# e-book_schema_v21.net
KiCad netlist of a schematic drawn in EAGLE
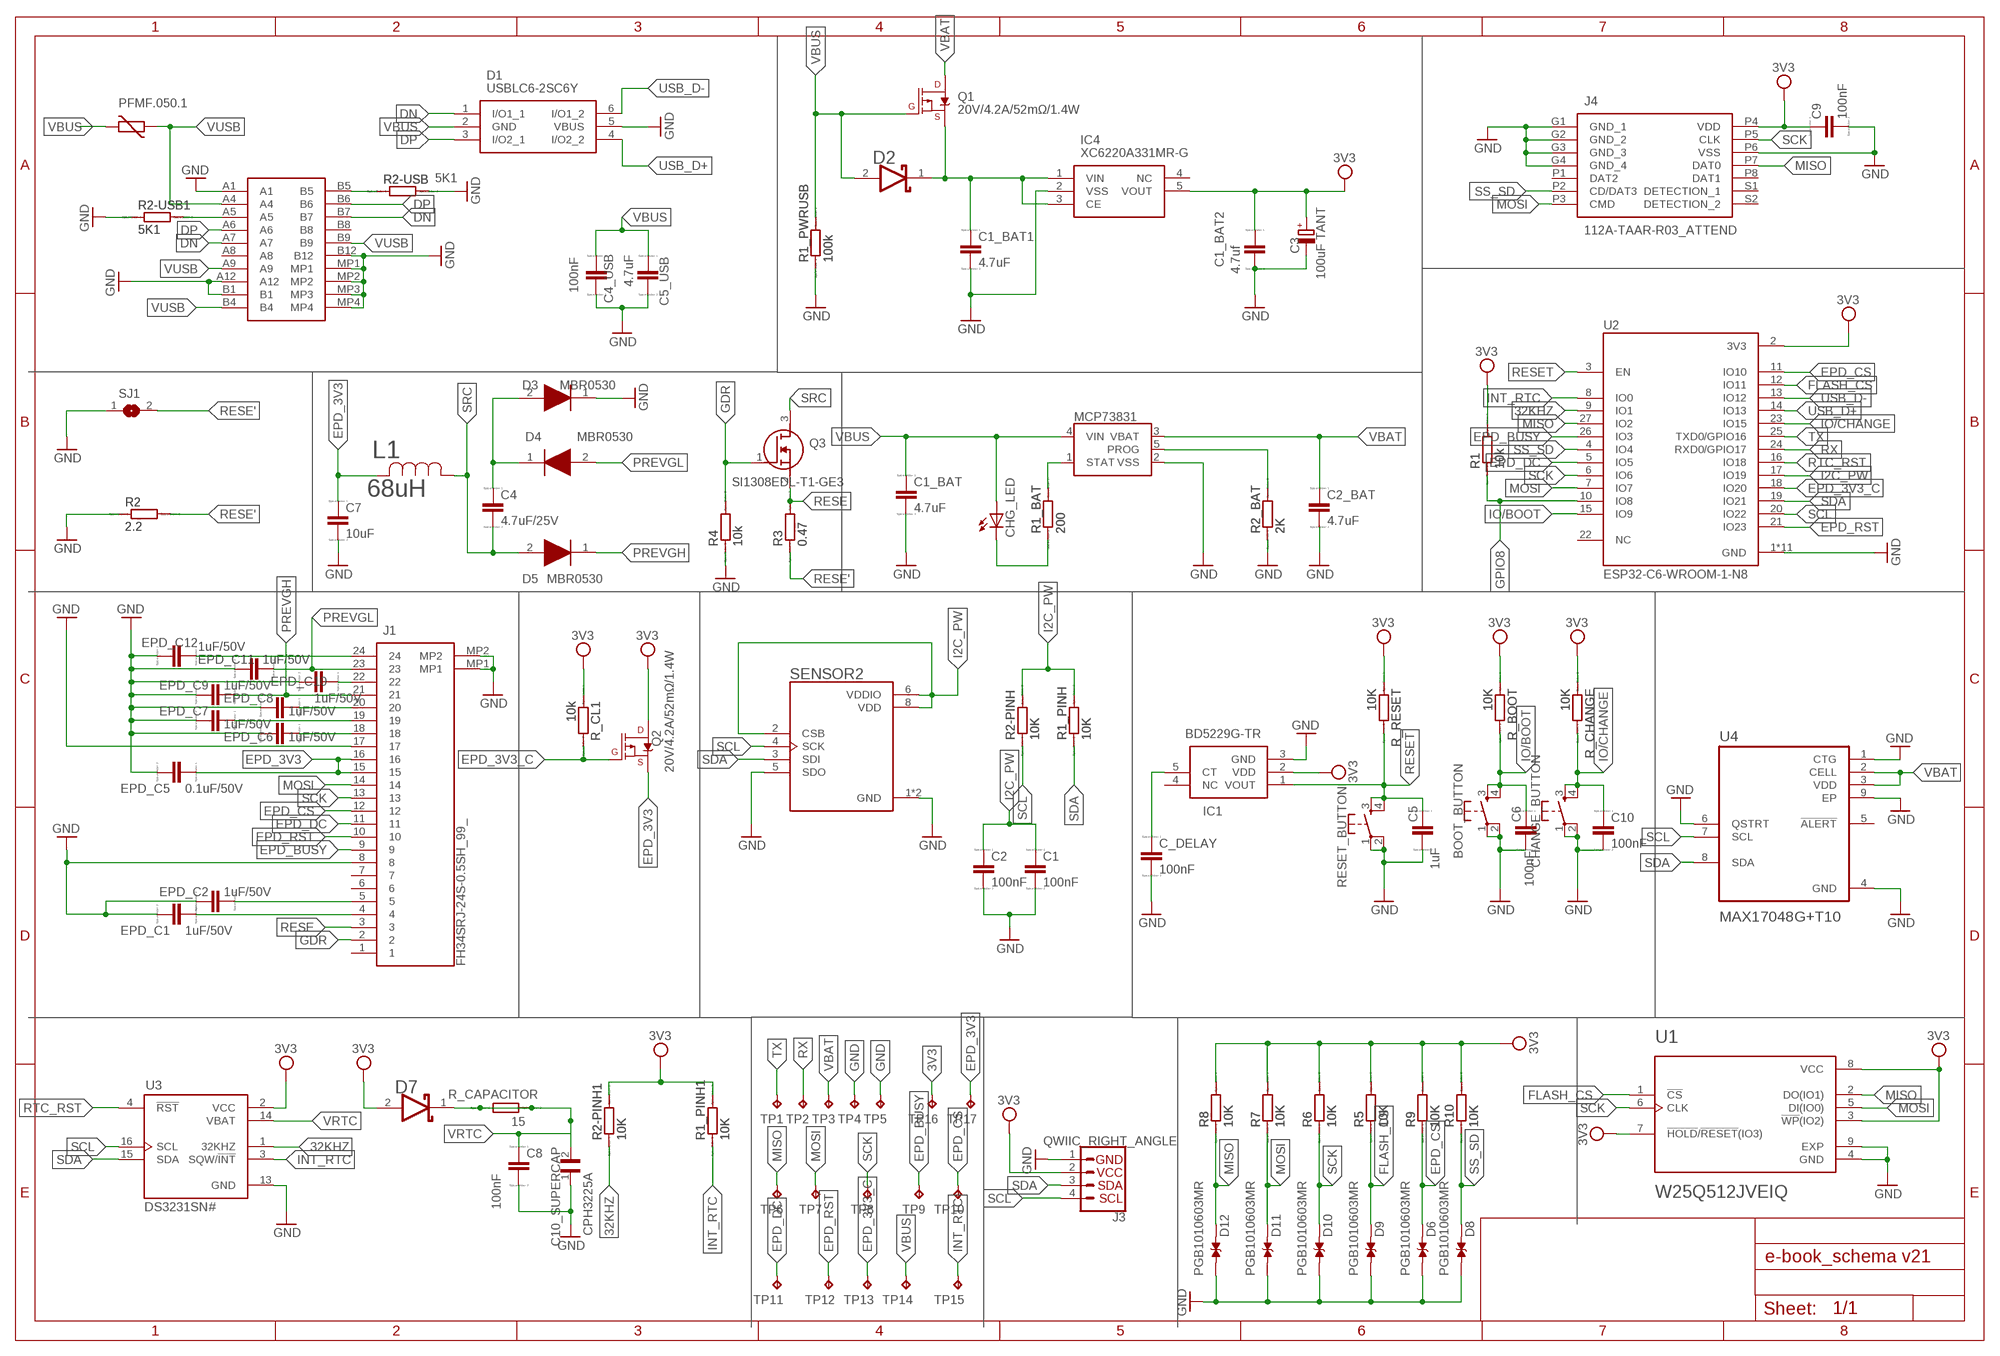
[diagram p0: schematic, sheet 1]

(export (version "E")
  (design (tool "Eeschema 10.0.6"))
  (components
    (comp (ref "BOOT_BUTTON")
      (value "BUTTON_CUSYOMV1")
      (footprint "eagle-import:MYBUTTON")
      (libsource (lib "eagle-import") (part "BUTTON_CUSYOMV1"))
    )
    (comp (ref "C1")
      (value "100nF")
      (footprint "eagle-import:EAGLE-LTSPICE_C0402")
      (libsource (lib "eagle-import") (part "EAGLE-LTSPICE_CC0402"))
    )
    (comp (ref "C1_BAT")
      (value "4.7uF")
      (footprint "eagle-import:EAGLE-LTSPICE_C0402")
      (libsource (lib "eagle-import") (part "EAGLE-LTSPICE_CC0402"))
    )
    (comp (ref "C1_BAT1")
      (value "4.7uF")
      (footprint "eagle-import:EAGLE-LTSPICE_C0402")
      (libsource (lib "eagle-import") (part "EAGLE-LTSPICE_CC0402"))
    )
    (comp (ref "C1_BAT2")
      (value "4.7uf")
      (footprint "eagle-import:EAGLE-LTSPICE_C0402")
      (libsource (lib "eagle-import") (part "EAGLE-LTSPICE_CC0402"))
    )
    (comp (ref "C2")
      (value "100nF")
      (footprint "eagle-import:EAGLE-LTSPICE_C0402")
      (libsource (lib "eagle-import") (part "EAGLE-LTSPICE_CC0402"))
    )
    (comp (ref "C2_BAT")
      (value "4.7uF")
      (footprint "eagle-import:EAGLE-LTSPICE_C0402")
      (libsource (lib "eagle-import") (part "EAGLE-LTSPICE_CC0402"))
    )
    (comp (ref "C3")
      (value "100uF TANT")
      (footprint "eagle-import:RCL_CT3528")
      (libsource (lib "eagle-import") (part "RCL_CPOL-EUCT3528"))
    )
    (comp (ref "C4")
      (value "4.7uF/25V")
      (footprint "eagle-import:EAGLE-LTSPICE_C0402")
      (libsource (lib "eagle-import") (part "EAGLE-LTSPICE_CC0402"))
    )
    (comp (ref "C4_USB")
      (value "100nF")
      (footprint "eagle-import:EAGLE-LTSPICE_C0402")
      (libsource (lib "eagle-import") (part "EAGLE-LTSPICE_CC0402"))
    )
    (comp (ref "C5")
      (value "1uF")
      (footprint "eagle-import:EAGLE-LTSPICE_C0402")
      (libsource (lib "eagle-import") (part "EAGLE-LTSPICE_CC0402"))
    )
    (comp (ref "C5_USB")
      (value "4.7uF")
      (footprint "eagle-import:EAGLE-LTSPICE_C0402")
      (libsource (lib "eagle-import") (part "EAGLE-LTSPICE_CC0402"))
    )
    (comp (ref "C6")
      (value "100nF")
      (footprint "eagle-import:EAGLE-LTSPICE_C0402")
      (libsource (lib "eagle-import") (part "EAGLE-LTSPICE_CC0402"))
    )
    (comp (ref "C7")
      (value "10uF")
      (footprint "eagle-import:EAGLE-LTSPICE_C0402")
      (libsource (lib "eagle-import") (part "EAGLE-LTSPICE_CC0402"))
    )
    (comp (ref "C8")
      (value "100nF")
      (footprint "eagle-import:EAGLE-LTSPICE_C0402")
      (libsource (lib "eagle-import") (part "EAGLE-LTSPICE_CC0402"))
    )
    (comp (ref "C9")
      (value "100nF")
      (footprint "eagle-import:EAGLE-LTSPICE_C0402")
      (libsource (lib "eagle-import") (part "EAGLE-LTSPICE_CC0402"))
    )
    (comp (ref "C10")
      (value "100nF")
      (footprint "eagle-import:EAGLE-LTSPICE_C0402")
      (libsource (lib "eagle-import") (part "EAGLE-LTSPICE_CC0402"))
    )
    (comp (ref "C10_SUPERCAP")
      (value "CPH3225A")
      (footprint "eagle-import:CAPCP3225X100N")
      (fields (field (name "MF") "Seiko Instruments"))
      (libsource (lib "eagle-import") (part "CPH3225A"))
    )
    (comp (ref "CHANGE_BUTTON")
      (value "BUTTON_CUSYOMV1")
      (footprint "eagle-import:MYBUTTON")
      (libsource (lib "eagle-import") (part "BUTTON_CUSYOMV1"))
    )
    (comp (ref "CHG_LED")
      (value "ADAFRUIT_LEDCHIP-LED0603")
      (footprint "eagle-import:ADAFRUIT_CHIP-LED0603")
      (libsource (lib "eagle-import") (part "ADAFRUIT_LEDCHIP-LED0603"))
    )
    (comp (ref "C_DELAY")
      (value "100nF")
      (footprint "eagle-import:EAGLE-LTSPICE_C0402")
      (libsource (lib "eagle-import") (part "EAGLE-LTSPICE_CC0402"))
    )
    (comp (ref "D1")
      (value "USBLC6-2SC6Y")
      (footprint "eagle-import:SOT95P280X145-6N")
      (fields (field (name "MF") "STMicroelectronics"))
      (libsource (lib "eagle-import") (part "USBLC6-2SC6Y"))
    )
    (comp (ref "D2")
      (value "ESP32_WROVER_AVX---SD0805S020S1R0_AVX_SD0805S020S1R0_0_0AVX_SD0805S020S1R0_0_0")
      (footprint "eagle-import:ESP32_WROVER_AVX---SD0805S020S1R0_AVX_SD0805S020S1R0_0")
      (fields
        (field (name "DIGIKEY_PART_NUMBER") "478-7800-1-ND")
        (field (name "MF") "AVX")
        (field (name "MOUSER_PART_NUMBER") "581-SD0805S020S1R0")
      )
      (libsource (lib "eagle-import") (part "ESP32_WROVER_AVX---SD0805S020S1R0_AVX_SD0805S020S1R0_0_0AVX_SD0805S020S1R0_0_0"))
    )
    (comp (ref "D3")
      (value "MBR0530")
      (footprint "eagle-import:SOD3716X135N")
      (fields (field (name "MF") "ON Semiconductor"))
      (libsource (lib "eagle-import") (part "MBR0530"))
    )
    (comp (ref "D4")
      (value "MBR0530")
      (footprint "eagle-import:SOD3716X135N")
      (fields (field (name "MF") "ON Semiconductor"))
      (libsource (lib "eagle-import") (part "MBR0530"))
    )
    (comp (ref "D5")
      (value "MBR0530")
      (footprint "eagle-import:SOD3716X135N")
      (fields (field (name "MF") "ON Semiconductor"))
      (libsource (lib "eagle-import") (part "MBR0530"))
    )
    (comp (ref "D6")
      (value "PGB1010603MR")
      (footprint "eagle-import:DIOC1608X36N")
      (fields (field (name "MF") "Littelfuse Inc."))
      (libsource (lib "eagle-import") (part "PGB1010603MR"))
    )
    (comp (ref "D7")
      (value "ESP32_WROVER_AVX---SD0805S020S1R0_AVX_SD0805S020S1R0_0_0AVX_SD0805S020S1R0_0_0")
      (footprint "eagle-import:ESP32_WROVER_AVX---SD0805S020S1R0_AVX_SD0805S020S1R0_0")
      (fields
        (field (name "DIGIKEY_PART_NUMBER") "478-7800-1-ND")
        (field (name "MF") "AVX")
        (field (name "MOUSER_PART_NUMBER") "581-SD0805S020S1R0")
      )
      (libsource (lib "eagle-import") (part "ESP32_WROVER_AVX---SD0805S020S1R0_AVX_SD0805S020S1R0_0_0AVX_SD0805S020S1R0_0_0"))
    )
    (comp (ref "D8")
      (value "PGB1010603MR")
      (footprint "eagle-import:DIOC1608X36N")
      (fields (field (name "MF") "Littelfuse Inc."))
      (libsource (lib "eagle-import") (part "PGB1010603MR"))
    )
    (comp (ref "D9")
      (value "PGB1010603MR")
      (footprint "eagle-import:DIOC1608X36N")
      (fields (field (name "MF") "Littelfuse Inc."))
      (libsource (lib "eagle-import") (part "PGB1010603MR"))
    )
    (comp (ref "D10")
      (value "PGB1010603MR")
      (footprint "eagle-import:DIOC1608X36N")
      (fields (field (name "MF") "Littelfuse Inc."))
      (libsource (lib "eagle-import") (part "PGB1010603MR"))
    )
    (comp (ref "D11")
      (value "PGB1010603MR")
      (footprint "eagle-import:DIOC1608X36N")
      (fields (field (name "MF") "Littelfuse Inc."))
      (libsource (lib "eagle-import") (part "PGB1010603MR"))
    )
    (comp (ref "D12")
      (value "PGB1010603MR")
      (footprint "eagle-import:DIOC1608X36N")
      (fields (field (name "MF") "Littelfuse Inc."))
      (libsource (lib "eagle-import") (part "PGB1010603MR"))
    )
    (comp (ref "EPD_C1")
      (value "1uF/50V")
      (footprint "eagle-import:EAGLE-LTSPICE_C0402")
      (libsource (lib "eagle-import") (part "EAGLE-LTSPICE_CC0402"))
    )
    (comp (ref "EPD_C2")
      (value "1uF/50V")
      (footprint "eagle-import:EAGLE-LTSPICE_C0402")
      (libsource (lib "eagle-import") (part "EAGLE-LTSPICE_CC0402"))
    )
    (comp (ref "EPD_C5")
      (value "0.1uF/50V")
      (footprint "eagle-import:EAGLE-LTSPICE_C0402")
      (libsource (lib "eagle-import") (part "EAGLE-LTSPICE_CC0402"))
    )
    (comp (ref "EPD_C6")
      (value "1uF/50V")
      (footprint "eagle-import:EAGLE-LTSPICE_C0402")
      (libsource (lib "eagle-import") (part "EAGLE-LTSPICE_CC0402"))
    )
    (comp (ref "EPD_C7")
      (value "1uF/50V")
      (footprint "eagle-import:EAGLE-LTSPICE_C0402")
      (libsource (lib "eagle-import") (part "EAGLE-LTSPICE_CC0402"))
    )
    (comp (ref "EPD_C8")
      (value "1uF/50V")
      (footprint "eagle-import:EAGLE-LTSPICE_C0402")
      (libsource (lib "eagle-import") (part "EAGLE-LTSPICE_CC0402"))
    )
    (comp (ref "EPD_C9")
      (value "1uF/50V")
      (footprint "eagle-import:EAGLE-LTSPICE_C0402")
      (libsource (lib "eagle-import") (part "EAGLE-LTSPICE_CC0402"))
    )
    (comp (ref "EPD_C10")
      (value "1uF/50V")
      (footprint "eagle-import:EAGLE-LTSPICE_C0402")
      (libsource (lib "eagle-import") (part "EAGLE-LTSPICE_CC0402"))
    )
    (comp (ref "EPD_C11")
      (value "1uF/50V")
      (footprint "eagle-import:EAGLE-LTSPICE_C0402")
      (libsource (lib "eagle-import") (part "EAGLE-LTSPICE_CC0402"))
    )
    (comp (ref "EPD_C12")
      (value "1uF/50V")
      (footprint "eagle-import:EAGLE-LTSPICE_C0402")
      (libsource (lib "eagle-import") (part "EAGLE-LTSPICE_CC0402"))
    )
    (comp (ref "IC1")
      (value "BD5229G-TR")
      (footprint "eagle-import:SOT95P280X125-5N")
      (fields (field (name "MOUSER_PART_NUMBER") "755-BD5229G-TR"))
      (libsource (lib "eagle-import") (part "BD5229G-TR"))
    )
    (comp (ref "IC4")
      (value "XC6220A331MR-G")
      (footprint "eagle-import:SOT95P280X120-5N")
      (fields (field (name "MOUSER_PART_NUMBER") "865-XC6220A331MR-G"))
      (libsource (lib "eagle-import") (part "XC6220A331MR-G"))
    )
    (comp (ref "J1")
      (value "FH34SRJ-24S-0.5SH_99_")
      (footprint "eagle-import:FH34SRJ24S05SH99")
      (fields
        (field (name "MANUFACTURER_PART_NUMBER") "FH34SRJ-24S-0.5SH(99)")
        (field (name "MOUSER_PART_NUMBER") "798-FH34SRJ24S05SH99")
      )
      (libsource (lib "eagle-import") (part "FH34SRJ-24S-0.5SH_99_"))
    )
    (comp (ref "J2")
      (value "SAMACSYS_PARTS_USB4110-GF-A")
      (footprint "eagle-import:SAMACSYS_PARTS_USB4110GFA")
      (fields
        (field (name "MANUFACTURER_PART_NUMBER") "USB4110-GF-A")
        (field (name "MOUSER_PART_NUMBER") "640-USB4110-GF-A")
      )
      (libsource (lib "eagle-import") (part "SAMACSYS_PARTS_USB4110-GF-A"))
    )
    (comp (ref "J3")
      (value "QWIIC_RIGHT_ANGLE")
      (footprint "eagle-import:JST04_1MM_RA")
      (libsource (lib "eagle-import") (part "QWIIC_CONNECTORJS-1MM"))
    )
    (comp (ref "J4")
      (value "112A-TAAR-R03_ATTEND")
      (footprint "eagle-import:112ATAARR03ATTEND")
      (fields (field (name "MANUFACTURER_PART_NUMBER") "112A-TAAR-R03 ATTEND"))
      (libsource (lib "eagle-import") (part "112A-TAAR-R03_ATTEND"))
    )
    (comp (ref "L1")
      (value "68uH")
      (footprint "eagle-import:IND_4828-WE-TPC_WRE")
      (fields
        (field (name "MANUFACTURER_PART_NUMBER") "744043680")
        (field (name "COPYRIGHT") "Copyright (C) 2024 Ultra Librarian. All rights reserved.")
      )
      (libsource (lib "eagle-import") (part "744043680IND_4828-WE-TPC_WRE"))
    )
    (comp (ref "MCP73831")
      (value "ESP32_WROVER_SPARKFUN-IC-POWER_MCP73831")
      (footprint "eagle-import:ESP32_WROVER_SPARKFUN-IC-POWER_SOT23-5")
      (libsource (lib "eagle-import") (part "ESP32_WROVER_SPARKFUN-IC-POWER_MCP73831"))
    )
    (comp (ref "PFMF.050.1")
      (value "ESP32C6_VARISTORCN1812")
      (footprint "eagle-import:ESP32C6_VARISTOR_CT_CN1812")
      (libsource (lib "eagle-import") (part "ESP32C6_VARISTORCN1812"))
    )
    (comp (ref "Q1")
      (value "20V/4.2A/52mΩ/1.4W")
      (footprint "eagle-import:ESP32_WROVER_SPARKFUN-DISCRETESEMI_SOT23-3")
      (libsource (lib "eagle-import") (part "ESP32_WROVER_SPARKFUN-DISCRETESEMI_MOSFET_PCH-DMG2305UX-7"))
    )
    (comp (ref "Q2")
      (value "20V/4.2A/52mΩ/1.4W")
      (footprint "eagle-import:ESP32_WROVER_SPARKFUN-DISCRETESEMI_SOT23-3")
      (libsource (lib "eagle-import") (part "ESP32_WROVER_SPARKFUN-DISCRETESEMI_MOSFET_PCH-DMG2305UX-7"))
    )
    (comp (ref "Q3")
      (value "SI1308EDL-T1-GE3")
      (footprint "eagle-import:SOT65P210X110-3N")
      (fields (field (name "MF") "Vishay Siliconix"))
      (libsource (lib "eagle-import") (part "SI1308EDL-T1-GE3"))
    )
    (comp (ref "R1")
      (value "10k")
      (footprint "eagle-import:ESP32_WROVER_EAGLE-LTSPICE_R0402")
      (libsource (lib "eagle-import") (part "ESP32_WROVER_EAGLE-LTSPICE_RR0402"))
    )
    (comp (ref "R1_BAT")
      (value "200")
      (footprint "eagle-import:ESP32_WROVER_EAGLE-LTSPICE_R0402")
      (libsource (lib "eagle-import") (part "ESP32_WROVER_EAGLE-LTSPICE_RR0402"))
    )
    (comp (ref "R1_PINH")
      (value "10K")
      (footprint "eagle-import:ESP32_WROVER_EAGLE-LTSPICE_R0402")
      (libsource (lib "eagle-import") (part "ESP32_WROVER_EAGLE-LTSPICE_RR0402"))
    )
    (comp (ref "R1_PINH1")
      (value "10K")
      (footprint "eagle-import:ESP32_WROVER_EAGLE-LTSPICE_R0402")
      (libsource (lib "eagle-import") (part "ESP32_WROVER_EAGLE-LTSPICE_RR0402"))
    )
    (comp (ref "R1_PWRUSB")
      (value "100k")
      (footprint "eagle-import:ESP32_WROVER_EAGLE-LTSPICE_R0402")
      (libsource (lib "eagle-import") (part "ESP32_WROVER_EAGLE-LTSPICE_RR0402"))
    )
    (comp (ref "R2")
      (value "2.2")
      (footprint "eagle-import:ESP32_WROVER_EAGLE-LTSPICE_R0402")
      (libsource (lib "eagle-import") (part "ESP32_WROVER_EAGLE-LTSPICE_RR0402"))
    )
    (comp (ref "R2-PINH")
      (value "10K")
      (footprint "eagle-import:ESP32_WROVER_EAGLE-LTSPICE_R0402")
      (libsource (lib "eagle-import") (part "ESP32_WROVER_EAGLE-LTSPICE_RR0402"))
    )
    (comp (ref "R2-PINH1")
      (value "10K")
      (footprint "eagle-import:ESP32_WROVER_EAGLE-LTSPICE_R0402")
      (libsource (lib "eagle-import") (part "ESP32_WROVER_EAGLE-LTSPICE_RR0402"))
    )
    (comp (ref "R2-USB")
      (value "5K1")
      (footprint "eagle-import:ESP32_WROVER_EAGLE-LTSPICE_R0402")
      (libsource (lib "eagle-import") (part "ESP32_WROVER_EAGLE-LTSPICE_RR0402"))
    )
    (comp (ref "R2-USB1")
      (value "5K1")
      (footprint "eagle-import:ESP32_WROVER_EAGLE-LTSPICE_R0402")
      (libsource (lib "eagle-import") (part "ESP32_WROVER_EAGLE-LTSPICE_RR0402"))
    )
    (comp (ref "R2_BAT")
      (value "2K")
      (footprint "eagle-import:ESP32_WROVER_EAGLE-LTSPICE_R0402")
      (libsource (lib "eagle-import") (part "ESP32_WROVER_EAGLE-LTSPICE_RR0402"))
    )
    (comp (ref "R3")
      (value "0.47")
      (footprint "eagle-import:ESP32_WROVER_EAGLE-LTSPICE_R0402")
      (libsource (lib "eagle-import") (part "ESP32_WROVER_EAGLE-LTSPICE_RR0402"))
    )
    (comp (ref "R4")
      (value "10k")
      (footprint "eagle-import:ESP32_WROVER_EAGLE-LTSPICE_R0402")
      (libsource (lib "eagle-import") (part "ESP32_WROVER_EAGLE-LTSPICE_RR0402"))
    )
    (comp (ref "R5")
      (value "10K")
      (footprint "eagle-import:ESP32_WROVER_EAGLE-LTSPICE_R0402")
      (libsource (lib "eagle-import") (part "ESP32_WROVER_EAGLE-LTSPICE_RR0402"))
    )
    (comp (ref "R6")
      (value "10K")
      (footprint "eagle-import:ESP32_WROVER_EAGLE-LTSPICE_R0402")
      (libsource (lib "eagle-import") (part "ESP32_WROVER_EAGLE-LTSPICE_RR0402"))
    )
    (comp (ref "R7")
      (value "10K")
      (footprint "eagle-import:ESP32_WROVER_EAGLE-LTSPICE_R0402")
      (libsource (lib "eagle-import") (part "ESP32_WROVER_EAGLE-LTSPICE_RR0402"))
    )
    (comp (ref "R8")
      (value "10K")
      (footprint "eagle-import:ESP32_WROVER_EAGLE-LTSPICE_R0402")
      (libsource (lib "eagle-import") (part "ESP32_WROVER_EAGLE-LTSPICE_RR0402"))
    )
    (comp (ref "R9")
      (value "10K")
      (footprint "eagle-import:ESP32_WROVER_EAGLE-LTSPICE_R0402")
      (libsource (lib "eagle-import") (part "ESP32_WROVER_EAGLE-LTSPICE_RR0402"))
    )
    (comp (ref "R10")
      (value "10K")
      (footprint "eagle-import:ESP32_WROVER_EAGLE-LTSPICE_R0402")
      (libsource (lib "eagle-import") (part "ESP32_WROVER_EAGLE-LTSPICE_RR0402"))
    )
    (comp (ref "RESET_BUTTON")
      (value "BUTTON_CUSYOMV1")
      (footprint "eagle-import:MYBUTTON")
      (libsource (lib "eagle-import") (part "BUTTON_CUSYOMV1"))
    )
    (comp (ref "R_BOOT")
      (value "10K")
      (footprint "eagle-import:ESP32_WROVER_EAGLE-LTSPICE_R0402")
      (libsource (lib "eagle-import") (part "ESP32_WROVER_EAGLE-LTSPICE_RR0402"))
    )
    (comp (ref "R_CAPACITOR")
      (value "15")
      (footprint "eagle-import:ESP32_WROVER_EAGLE-LTSPICE_R0402")
      (libsource (lib "eagle-import") (part "ESP32_WROVER_EAGLE-LTSPICE_RR0402"))
    )
    (comp (ref "R_CHANGE")
      (value "10K")
      (footprint "eagle-import:ESP32_WROVER_EAGLE-LTSPICE_R0402")
      (libsource (lib "eagle-import") (part "ESP32_WROVER_EAGLE-LTSPICE_RR0402"))
    )
    (comp (ref "R_CL1")
      (value "10k")
      (footprint "eagle-import:ESP32_WROVER_EAGLE-LTSPICE_R0402")
      (libsource (lib "eagle-import") (part "ESP32_WROVER_EAGLE-LTSPICE_RR0402"))
    )
    (comp (ref "R_RESET")
      (value "10K")
      (footprint "eagle-import:ESP32_WROVER_EAGLE-LTSPICE_R0402")
      (libsource (lib "eagle-import") (part "ESP32_WROVER_EAGLE-LTSPICE_RR0402"))
    )
    (comp (ref "SENSOR2")
      (value "ESP32_WROVER_BME680_BME680")
      (footprint "eagle-import:ESP32_WROVER_BME680_PSON80P300X300X100-8N")
      (fields (field (name "MF") "Bosch Sensortec") (field (name "MP") "BME680"))
      (libsource (lib "eagle-import") (part "ESP32_WROVER_BME680_BME680"))
    )
    (comp (ref "SJ1") (value "SJ") (footprint "eagle-import:SJ") (libsource (lib "eagle-import") (part "SJ")))
    (comp (ref "TP1")
      (value "TPTP20R")
      (footprint "eagle-import:TP20R")
      (libsource (lib "eagle-import") (part "TPTP20R"))
    )
    (comp (ref "TP2")
      (value "TPTP20R")
      (footprint "eagle-import:TP20R")
      (libsource (lib "eagle-import") (part "TPTP20R"))
    )
    (comp (ref "TP3")
      (value "TPTP20R")
      (footprint "eagle-import:TP20R")
      (libsource (lib "eagle-import") (part "TPTP20R"))
    )
    (comp (ref "TP4")
      (value "TPTP20R")
      (footprint "eagle-import:TP20R")
      (libsource (lib "eagle-import") (part "TPTP20R"))
    )
    (comp (ref "TP5")
      (value "TPTP20R")
      (footprint "eagle-import:TP20R")
      (libsource (lib "eagle-import") (part "TPTP20R"))
    )
    (comp (ref "TP6")
      (value "TPTP20R")
      (footprint "eagle-import:TP20R")
      (libsource (lib "eagle-import") (part "TPTP20R"))
    )
    (comp (ref "TP7")
      (value "TPTP20R")
      (footprint "eagle-import:TP20R")
      (libsource (lib "eagle-import") (part "TPTP20R"))
    )
    (comp (ref "TP8")
      (value "TPTP20R")
      (footprint "eagle-import:TP20R")
      (libsource (lib "eagle-import") (part "TPTP20R"))
    )
    (comp (ref "TP9")
      (value "TPTP20R")
      (footprint "eagle-import:TP20R")
      (libsource (lib "eagle-import") (part "TPTP20R"))
    )
    (comp (ref "TP10")
      (value "TPTP20R")
      (footprint "eagle-import:TP20R")
      (libsource (lib "eagle-import") (part "TPTP20R"))
    )
    (comp (ref "TP11")
      (value "TPTP20R")
      (footprint "eagle-import:TP20R")
      (libsource (lib "eagle-import") (part "TPTP20R"))
    )
    (comp (ref "TP12")
      (value "TPTP20R")
      (footprint "eagle-import:TP20R")
      (libsource (lib "eagle-import") (part "TPTP20R"))
    )
    (comp (ref "TP13")
      (value "TPTP20R")
      (footprint "eagle-import:TP20R")
      (libsource (lib "eagle-import") (part "TPTP20R"))
    )
    (comp (ref "TP14")
      (value "TPTP20R")
      (footprint "eagle-import:TP20R")
      (libsource (lib "eagle-import") (part "TPTP20R"))
    )
    (comp (ref "TP15")
      (value "TPTP20R")
      (footprint "eagle-import:TP20R")
      (libsource (lib "eagle-import") (part "TPTP20R"))
    )
    (comp (ref "TP16")
      (value "TPTP20R")
      (footprint "eagle-import:TP20R")
      (libsource (lib "eagle-import") (part "TPTP20R"))
    )
    (comp (ref "TP17")
      (value "TPTP20R")
      (footprint "eagle-import:TP20R")
      (libsource (lib "eagle-import") (part "TPTP20R"))
    )
    (comp (ref "U1")
      (value "W25Q512JVEIQ")
      (footprint "eagle-import:SON127P600X800X80-9N")
      (fields (field (name "MF") "Winbond Electronics"))
      (libsource (lib "eagle-import") (part "W25Q512JVEIQ"))
    )
    (comp (ref "U2")
      (value "ESP32-C6-WROOM-1-N8")
      (footprint "eagle-import:XCVR_ESP32-C6-WROOM-1-N8")
      (fields (field (name "MF") "Espressif Systems"))
      (libsource (lib "eagle-import") (part "ESP32-C6-WROOM-1-N8"))
    )
    (comp (ref "U3")
      (value "DS3231SN#")
      (footprint "eagle-import:SOIC127P1032X265-16N")
      (fields (field (name "MF") "Analog Devices"))
      (libsource (lib "eagle-import") (part "DS3231SN#"))
    )
    (comp (ref "U4")
      (value "MAX17048G+T10")
      (footprint "eagle-import:SON50P200X200X80-9N")
      (fields (field (name "MF") "Analog Devices"))
      (libsource (lib "eagle-import") (part "MAX17048G+T10"))
    )
  )
  (nets
    (net (code "1") (name "3V3") (class "Default")
      (node (ref "C1_BAT2") (pin "1") (pinfunction "1_1") (pintype "passive"))
      (node (ref "C3") (pin "+") (pinfunction "+_+") (pintype "passive"))
      (node (ref "C9") (pin "1") (pinfunction "1_1") (pintype "passive"))
      (node (ref "D7") (pin "2") (pinfunction "ANODE_2") (pintype "bidirectional"))
      (node (ref "IC1") (pin "2") (pinfunction "VDD_2") (pintype "bidirectional"))
      (node (ref "IC4") (pin "5") (pinfunction "VOUT_5") (pintype "bidirectional"))
      (node (ref "J3") (pin "2") (pinfunction "2_2") (pintype "power_in"))
      (node (ref "J4") (pin "P4") (pinfunction "VDD_P4") (pintype "bidirectional"))
      (node (ref "Q2") (pin "3") (pinfunction "D_3") (pintype "bidirectional"))
      (node (ref "R1") (pin "2") (pinfunction "2_2") (pintype "passive"))
      (node (ref "R10") (pin "2") (pinfunction "2_2") (pintype "passive"))
      (node (ref "R1_PINH1") (pin "2") (pinfunction "2_2") (pintype "passive"))
      (node (ref "R2-PINH1") (pin "2") (pinfunction "2_2") (pintype "passive"))
      (node (ref "R5") (pin "2") (pinfunction "2_2") (pintype "passive"))
      (node (ref "R6") (pin "2") (pinfunction "2_2") (pintype "passive"))
      (node (ref "R7") (pin "2") (pinfunction "2_2") (pintype "passive"))
      (node (ref "R8") (pin "2") (pinfunction "2_2") (pintype "passive"))
      (node (ref "R9") (pin "2") (pinfunction "2_2") (pintype "passive"))
      (node (ref "R_BOOT") (pin "1") (pinfunction "1_1") (pintype "passive"))
      (node (ref "R_CHANGE") (pin "1") (pinfunction "1_1") (pintype "passive"))
      (node (ref "R_CL1") (pin "1") (pinfunction "1_1") (pintype "passive"))
      (node (ref "R_RESET") (pin "1") (pinfunction "1_1") (pintype "passive"))
      (node (ref "TP16") (pin "TP") (pinfunction "TP_TP") (pintype "input"))
      (node (ref "U1") (pin "3") (pinfunction "~{WP}(IO2)_3") (pintype "bidirectional"))
      (node (ref "U1") (pin "7") (pinfunction "~{HOLD}/~{RESET}(IO3)_7") (pintype "bidirectional"))
      (node (ref "U1") (pin "8") (pinfunction "VCC_8") (pintype "power_in"))
      (node (ref "U2") (pin "2") (pinfunction "3V3_2") (pintype "power_in"))
      (node (ref "U3") (pin "2") (pinfunction "VCC_2") (pintype "power_in"))
    )
    (net (code "2") (name "32KHZ") (class "Default")
      (node (ref "R2-PINH1") (pin "1") (pinfunction "1_1") (pintype "passive"))
      (node (ref "U2") (pin "9") (pinfunction "IO1_9") (pintype "bidirectional"))
      (node (ref "U3") (pin "1") (pinfunction "32KHZ_1") (pintype "output"))
    )
    (net (code "3") (name "DN") (class "Default")
      (node (ref "D1") (pin "1") (pinfunction "I/O1_1_1") (pintype "bidirectional"))
      (node (ref "J2") (pin "A7") (pinfunction "A7_A7") (pintype "bidirectional"))
      (node (ref "J2") (pin "B7") (pinfunction "B7_B7") (pintype "bidirectional"))
    )
    (net (code "4") (name "DP") (class "Default")
      (node (ref "D1") (pin "3") (pinfunction "I/O2_1_3") (pintype "bidirectional"))
      (node (ref "J2") (pin "A6") (pinfunction "A6_A6") (pintype "bidirectional"))
      (node (ref "J2") (pin "B6") (pinfunction "B6_B6") (pintype "bidirectional"))
    )
    (net (code "5") (name "EPD_3V3") (class "Default")
      (node (ref "C7") (pin "1") (pinfunction "1_1") (pintype "passive"))
      (node (ref "EPD_C5") (pin "1") (pinfunction "1_1") (pintype "passive"))
      (node (ref "J1") (pin "15") (pinfunction "15_15") (pintype "bidirectional"))
      (node (ref "J1") (pin "16") (pinfunction "16_16") (pintype "bidirectional"))
      (node (ref "L1") (pin "2") (pinfunction "2_2") (pintype "passive"))
      (node (ref "Q2") (pin "2") (pinfunction "S_2") (pintype "bidirectional"))
      (node (ref "TP17") (pin "TP") (pinfunction "TP_TP") (pintype "input"))
    )
    (net (code "6") (name "EPD_3V3_C") (class "Default")
      (node (ref "Q2") (pin "1") (pinfunction "G_1") (pintype "bidirectional"))
      (node (ref "R_CL1") (pin "2") (pinfunction "2_2") (pintype "passive"))
      (node (ref "TP13") (pin "TP") (pinfunction "TP_TP") (pintype "input"))
      (node (ref "U2") (pin "18") (pinfunction "IO20_18") (pintype "bidirectional"))
    )
    (net (code "7") (name "EPD_BUSY") (class "Default")
      (node (ref "J1") (pin "9") (pinfunction "9_9") (pintype "bidirectional"))
      (node (ref "TP9") (pin "TP") (pinfunction "TP_TP") (pintype "input"))
      (node (ref "U2") (pin "26") (pinfunction "IO3_26") (pintype "bidirectional"))
    )
    (net (code "8") (name "EPD_CS") (class "Default")
      (node (ref "D6") (pin "2") (pinfunction "2_2") (pintype "passive"))
      (node (ref "J1") (pin "12") (pinfunction "12_12") (pintype "bidirectional"))
      (node (ref "R9") (pin "1") (pinfunction "1_1") (pintype "passive"))
      (node (ref "TP10") (pin "TP") (pinfunction "TP_TP") (pintype "input"))
      (node (ref "U2") (pin "11") (pinfunction "IO10_11") (pintype "bidirectional"))
    )
    (net (code "9") (name "EPD_DC") (class "Default")
      (node (ref "J1") (pin "11") (pinfunction "11_11") (pintype "bidirectional"))
      (node (ref "TP11") (pin "TP") (pinfunction "TP_TP") (pintype "input"))
      (node (ref "U2") (pin "5") (pinfunction "IO5_5") (pintype "bidirectional"))
    )
    (net (code "10") (name "EPD_RST") (class "Default")
      (node (ref "J1") (pin "10") (pinfunction "10_10") (pintype "bidirectional"))
      (node (ref "TP12") (pin "TP") (pinfunction "TP_TP") (pintype "input"))
      (node (ref "U2") (pin "21") (pinfunction "IO23_21") (pintype "bidirectional"))
    )
    (net (code "11") (name "FLASH_CS") (class "Default")
      (node (ref "D9") (pin "2") (pinfunction "2_2") (pintype "passive"))
      (node (ref "R5") (pin "1") (pinfunction "1_1") (pintype "passive"))
      (node (ref "U1") (pin "1") (pinfunction "~{CS}_1") (pintype "input"))
      (node (ref "U2") (pin "12") (pinfunction "IO11_12") (pintype "bidirectional"))
    )
    (net (code "12") (name "GDR") (class "Default")
      (node (ref "J1") (pin "2") (pinfunction "2_2") (pintype "bidirectional"))
      (node (ref "Q3") (pin "1") (pinfunction "G_1") (pintype "bidirectional"))
      (node (ref "R4") (pin "2") (pinfunction "2_2") (pintype "passive"))
    )
    (net (code "13") (name "GND") (class "Default")
      (node (ref "BOOT_BUTTON") (pin "1") (pinfunction "1_1") (pintype "passive"))
      (node (ref "BOOT_BUTTON") (pin "2") (pinfunction "2_2") (pintype "passive"))
      (node (ref "C1") (pin "2") (pinfunction "2_2") (pintype "passive"))
      (node (ref "C10") (pin "2") (pinfunction "2_2") (pintype "passive"))
      (node (ref "C10_SUPERCAP") (pin "1") (pinfunction "1_1") (pintype "passive"))
      (node (ref "C1_BAT") (pin "2") (pinfunction "2_2") (pintype "passive"))
      (node (ref "C1_BAT1") (pin "2") (pinfunction "2_2") (pintype "passive"))
      (node (ref "C1_BAT2") (pin "2") (pinfunction "2_2") (pintype "passive"))
      (node (ref "C2") (pin "2") (pinfunction "2_2") (pintype "passive"))
      (node (ref "C2_BAT") (pin "2") (pinfunction "2_2") (pintype "passive"))
      (node (ref "C3") (pin "-") (pinfunction "-_-") (pintype "passive"))
      (node (ref "C4_USB") (pin "2") (pinfunction "2_2") (pintype "passive"))
      (node (ref "C5") (pin "2") (pinfunction "2_2") (pintype "passive"))
      (node (ref "C5_USB") (pin "2") (pinfunction "2_2") (pintype "passive"))
      (node (ref "C6") (pin "2") (pinfunction "2_2") (pintype "passive"))
      (node (ref "C7") (pin "2") (pinfunction "2_2") (pintype "passive"))
      (node (ref "C8") (pin "2") (pinfunction "2_2") (pintype "passive"))
      (node (ref "C9") (pin "2") (pinfunction "2_2") (pintype "passive"))
      (node (ref "CHANGE_BUTTON") (pin "1") (pinfunction "1_1") (pintype "passive"))
      (node (ref "CHANGE_BUTTON") (pin "2") (pinfunction "2_2") (pintype "passive"))
      (node (ref "C_DELAY") (pin "2") (pinfunction "2_2") (pintype "passive"))
      (node (ref "D1") (pin "5") (pinfunction "VBUS_5") (pintype "bidirectional"))
      (node (ref "D10") (pin "1") (pinfunction "1_1") (pintype "passive"))
      (node (ref "D11") (pin "1") (pinfunction "1_1") (pintype "passive"))
      (node (ref "D12") (pin "1") (pinfunction "1_1") (pintype "passive"))
      (node (ref "D3") (pin "1") (pinfunction "K_1") (pintype "bidirectional"))
      (node (ref "D6") (pin "1") (pinfunction "1_1") (pintype "passive"))
      (node (ref "D8") (pin "1") (pinfunction "1_1") (pintype "passive"))
      (node (ref "D9") (pin "1") (pinfunction "1_1") (pintype "passive"))
      (node (ref "EPD_C1") (pin "2") (pinfunction "2_2") (pintype "passive"))
      (node (ref "EPD_C10") (pin "2") (pinfunction "2_2") (pintype "passive"))
      (node (ref "EPD_C11") (pin "2") (pinfunction "2_2") (pintype "passive"))
      (node (ref "EPD_C12") (pin "2") (pinfunction "2_2") (pintype "passive"))
      (node (ref "EPD_C2") (pin "2") (pinfunction "2_2") (pintype "passive"))
      (node (ref "EPD_C5") (pin "2") (pinfunction "2_2") (pintype "passive"))
      (node (ref "EPD_C6") (pin "2") (pinfunction "2_2") (pintype "passive"))
      (node (ref "EPD_C7") (pin "2") (pinfunction "2_2") (pintype "passive"))
      (node (ref "EPD_C8") (pin "2") (pinfunction "2_2") (pintype "passive"))
      (node (ref "EPD_C9") (pin "2") (pinfunction "2_2") (pintype "passive"))
      (node (ref "IC1") (pin "3") (pinfunction "GND_3") (pintype "bidirectional"))
      (node (ref "IC4") (pin "2") (pinfunction "VSS_2") (pintype "bidirectional"))
      (node (ref "J1") (pin "17") (pinfunction "17_17") (pintype "bidirectional"))
      (node (ref "J1") (pin "8") (pinfunction "8_8") (pintype "bidirectional"))
      (node (ref "J1") (pin "MP1") (pinfunction "MP1_MP1") (pintype "bidirectional"))
      (node (ref "J1") (pin "MP2") (pinfunction "MP2_MP2") (pintype "bidirectional"))
      (node (ref "J2") (pin "A1") (pinfunction "A1_A1") (pintype "bidirectional"))
      (node (ref "J2") (pin "A12") (pinfunction "A12_A12") (pintype "bidirectional"))
      (node (ref "J2") (pin "B1") (pinfunction "B1_B1") (pintype "bidirectional"))
      (node (ref "J2") (pin "B12") (pinfunction "B12_B12") (pintype "bidirectional"))
      (node (ref "J2") (pin "MP1") (pinfunction "MP1_MP1") (pintype "bidirectional"))
      (node (ref "J2") (pin "MP2") (pinfunction "MP2_MP2") (pintype "bidirectional"))
      (node (ref "J2") (pin "MP3") (pinfunction "MP3_MP3") (pintype "bidirectional"))
      (node (ref "J2") (pin "MP4") (pinfunction "MP4_MP4") (pintype "bidirectional"))
      (node (ref "J3") (pin "1") (pinfunction "1_1") (pintype "power_in"))
      (node (ref "J4") (pin "G1") (pinfunction "GND_1_G1") (pintype "bidirectional"))
      (node (ref "J4") (pin "G2") (pinfunction "GND_2_G2") (pintype "bidirectional"))
      (node (ref "J4") (pin "G3") (pinfunction "GND_3_G3") (pintype "bidirectional"))
      (node (ref "J4") (pin "G4") (pinfunction "GND_4_G4") (pintype "bidirectional"))
      (node (ref "J4") (pin "P6") (pinfunction "VSS_P6") (pintype "bidirectional"))
      (node (ref "MCP73831") (pin "2") (pinfunction "VSS_2") (pintype "power_in"))
      (node (ref "R1_PWRUSB") (pin "1") (pinfunction "1_1") (pintype "passive"))
      (node (ref "R2") (pin "1") (pinfunction "1_1") (pintype "passive"))
      (node (ref "R2-USB") (pin "2") (pinfunction "2_2") (pintype "passive"))
      (node (ref "R2-USB1") (pin "1") (pinfunction "1_1") (pintype "passive"))
      (node (ref "R2_BAT") (pin "1") (pinfunction "1_1") (pintype "passive"))
      (node (ref "R4") (pin "1") (pinfunction "1_1") (pintype "passive"))
      (node (ref "RESET_BUTTON") (pin "1") (pinfunction "1_1") (pintype "passive"))
      (node (ref "RESET_BUTTON") (pin "2") (pinfunction "2_2") (pintype "passive"))
      (node (ref "SENSOR2") (pin "1") (pinfunction "GND_1") (pintype "power_in"))
      (node (ref "SENSOR2") (pin "5") (pinfunction "SDO_5") (pintype "bidirectional"))
      (node (ref "SENSOR2") (pin "7") (pinfunction "GND_7") (pintype "power_in"))
      (node (ref "SJ1") (pin "1") (pinfunction "1_1") (pintype "passive"))
      (node (ref "TP4") (pin "TP") (pinfunction "TP_TP") (pintype "input"))
      (node (ref "TP5") (pin "TP") (pinfunction "TP_TP") (pintype "input"))
      (node (ref "U1") (pin "4") (pinfunction "GND_4") (pintype "power_in"))
      (node (ref "U1") (pin "9") (pinfunction "EXP_9") (pintype "passive"))
      (node (ref "U2") (pin "1") (pinfunction "GND_1") (pintype "power_in"))
      (node (ref "U2") (pin "28") (pinfunction "GND_28") (pintype "power_in"))
      (node (ref "U2") (pin "29_1") (pinfunction "GND_29_1") (pintype "power_in"))
      (node (ref "U2") (pin "29_2") (pinfunction "GND_29_2") (pintype "power_in"))
      (node (ref "U2") (pin "29_3") (pinfunction "GND_29_3") (pintype "power_in"))
      (node (ref "U2") (pin "29_4") (pinfunction "GND_29_4") (pintype "power_in"))
      (node (ref "U2") (pin "29_5") (pinfunction "GND_29_5") (pintype "power_in"))
      (node (ref "U2") (pin "29_6") (pinfunction "GND_29_6") (pintype "power_in"))
      (node (ref "U2") (pin "29_7") (pinfunction "GND_29_7") (pintype "power_in"))
      (node (ref "U2") (pin "29_8") (pinfunction "GND_29_8") (pintype "power_in"))
      (node (ref "U2") (pin "29_9") (pinfunction "GND_29_9") (pintype "power_in"))
      (node (ref "U3") (pin "13") (pinfunction "GND_13") (pintype "power_in"))
      (node (ref "U4") (pin "1") (pinfunction "CTG_1") (pintype "power_in"))
      (node (ref "U4") (pin "4") (pinfunction "GND_4") (pintype "power_in"))
      (node (ref "U4") (pin "6") (pinfunction "QSTRT_6") (pintype "input"))
      (node (ref "U4") (pin "9") (pinfunction "EP_9") (pintype "power_in"))
    )
    (net (code "14") (name "GPIO8") (class "Default")
      (node (ref "R1") (pin "1") (pinfunction "1_1") (pintype "passive"))
      (node (ref "U2") (pin "10") (pinfunction "IO8_10") (pintype "bidirectional"))
    )
    (net (code "15") (name "I2C_PW") (class "Default")
      (node (ref "C1") (pin "1") (pinfunction "1_1") (pintype "passive"))
      (node (ref "C2") (pin "1") (pinfunction "1_1") (pintype "passive"))
      (node (ref "R1_PINH") (pin "2") (pinfunction "2_2") (pintype "passive"))
      (node (ref "R2-PINH") (pin "2") (pinfunction "2_2") (pintype "passive"))
      (node (ref "SENSOR2") (pin "2") (pinfunction "CSB_2") (pintype "input"))
      (node (ref "SENSOR2") (pin "6") (pinfunction "VDDIO_6") (pintype "power_in"))
      (node (ref "SENSOR2") (pin "8") (pinfunction "VDD_8") (pintype "power_in"))
      (node (ref "U2") (pin "17") (pinfunction "IO19_17") (pintype "bidirectional"))
    )
    (net (code "16") (name "INT_RTC") (class "Default")
      (node (ref "R1_PINH1") (pin "1") (pinfunction "1_1") (pintype "passive"))
      (node (ref "TP15") (pin "TP") (pinfunction "TP_TP") (pintype "input"))
      (node (ref "U2") (pin "8") (pinfunction "IO0_8") (pintype "bidirectional"))
      (node (ref "U3") (pin "3") (pinfunction "SQW/~{INT}_3") (pintype "output"))
    )
    (net (code "17") (name "IO{slash}BOOT") (class "Default")
      (node (ref "BOOT_BUTTON") (pin "3") (pinfunction "3_3") (pintype "passive"))
      (node (ref "BOOT_BUTTON") (pin "4") (pinfunction "4_4") (pintype "passive"))
      (node (ref "C6") (pin "1") (pinfunction "1_1") (pintype "passive"))
      (node (ref "R_BOOT") (pin "2") (pinfunction "2_2") (pintype "passive"))
      (node (ref "U2") (pin "15") (pinfunction "IO9_15") (pintype "bidirectional"))
    )
    (net (code "18") (name "IO{slash}CHANGE") (class "Default")
      (node (ref "C10") (pin "1") (pinfunction "1_1") (pintype "passive"))
      (node (ref "CHANGE_BUTTON") (pin "3") (pinfunction "3_3") (pintype "passive"))
      (node (ref "CHANGE_BUTTON") (pin "4") (pinfunction "4_4") (pintype "passive"))
      (node (ref "R_CHANGE") (pin "2") (pinfunction "2_2") (pintype "passive"))
      (node (ref "U2") (pin "23") (pinfunction "IO15_23") (pintype "bidirectional"))
    )
    (net (code "19") (name "MISO") (class "Default")
      (node (ref "D12") (pin "2") (pinfunction "2_2") (pintype "passive"))
      (node (ref "J4") (pin "P7") (pinfunction "DAT0_P7") (pintype "bidirectional"))
      (node (ref "R8") (pin "1") (pinfunction "1_1") (pintype "passive"))
      (node (ref "TP6") (pin "TP") (pinfunction "TP_TP") (pintype "input"))
      (node (ref "U1") (pin "2") (pinfunction "DO(IO1)_2") (pintype "bidirectional"))
      (node (ref "U2") (pin "27") (pinfunction "IO2_27") (pintype "bidirectional"))
    )
    (net (code "20") (name "MOSI") (class "Default")
      (node (ref "D11") (pin "2") (pinfunction "2_2") (pintype "passive"))
      (node (ref "J1") (pin "14") (pinfunction "14_14") (pintype "bidirectional"))
      (node (ref "J4") (pin "P3") (pinfunction "CMD_P3") (pintype "bidirectional"))
      (node (ref "R7") (pin "1") (pinfunction "1_1") (pintype "passive"))
      (node (ref "TP7") (pin "TP") (pinfunction "TP_TP") (pintype "input"))
      (node (ref "U1") (pin "5") (pinfunction "DI(IO0)_5") (pintype "bidirectional"))
      (node (ref "U2") (pin "7") (pinfunction "IO7_7") (pintype "bidirectional"))
    )
    (net (code "21") (name "Net-(CHG_LED-PadC)") (class "Default")
      (node (ref "CHG_LED") (pin "C") (pinfunction "C_C") (pintype "passive"))
      (node (ref "R1_BAT") (pin "1") (pinfunction "1_1") (pintype "passive"))
    )
    (net (code "22") (name "Net-(D2-CATHODE)") (class "Default")
      (node (ref "C1_BAT1") (pin "1") (pinfunction "1_1") (pintype "passive"))
      (node (ref "D2") (pin "1") (pinfunction "CATHODE_1") (pintype "bidirectional"))
      (node (ref "IC4") (pin "1") (pinfunction "VIN_1") (pintype "bidirectional"))
      (node (ref "IC4") (pin "3") (pinfunction "CE_3") (pintype "bidirectional"))
      (node (ref "Q1") (pin "2") (pinfunction "S_2") (pintype "bidirectional"))
    )
    (net (code "23") (name "Net-(D3-A)") (class "Default")
      (node (ref "C4") (pin "1") (pinfunction "1_1") (pintype "passive"))
      (node (ref "D3") (pin "2") (pinfunction "A_2") (pintype "bidirectional"))
      (node (ref "D4") (pin "1") (pinfunction "K_1") (pintype "bidirectional"))
    )
    (net (code "24") (name "Net-(EPD_C1-Pad1)") (class "Default")
      (node (ref "EPD_C1") (pin "1") (pinfunction "1_1") (pintype "passive"))
      (node (ref "J1") (pin "4") (pinfunction "4_4") (pintype "bidirectional"))
    )
    (net (code "25") (name "Net-(EPD_C2-Pad1)") (class "Default")
      (node (ref "EPD_C2") (pin "1") (pinfunction "1_1") (pintype "passive"))
      (node (ref "J1") (pin "5") (pinfunction "5_5") (pintype "bidirectional"))
    )
    (net (code "26") (name "Net-(EPD_C6-Pad1)") (class "Default")
      (node (ref "EPD_C6") (pin "1") (pinfunction "1_1") (pintype "passive"))
      (node (ref "J1") (pin "18") (pinfunction "18_18") (pintype "bidirectional"))
    )
    (net (code "27") (name "Net-(EPD_C7-Pad1)") (class "Default")
      (node (ref "EPD_C7") (pin "1") (pinfunction "1_1") (pintype "passive"))
      (node (ref "J1") (pin "19") (pinfunction "19_19") (pintype "bidirectional"))
    )
    (net (code "28") (name "Net-(EPD_C8-Pad1)") (class "Default")
      (node (ref "EPD_C8") (pin "1") (pinfunction "1_1") (pintype "passive"))
      (node (ref "J1") (pin "20") (pinfunction "20_20") (pintype "bidirectional"))
    )
    (net (code "29") (name "Net-(EPD_C10-Pad1)") (class "Default")
      (node (ref "EPD_C10") (pin "1") (pinfunction "1_1") (pintype "passive"))
      (node (ref "J1") (pin "22") (pinfunction "22_22") (pintype "bidirectional"))
    )
    (net (code "30") (name "Net-(EPD_C12-Pad1)") (class "Default")
      (node (ref "EPD_C12") (pin "1") (pinfunction "1_1") (pintype "passive"))
      (node (ref "J1") (pin "24") (pinfunction "24_24") (pintype "bidirectional"))
    )
    (net (code "31") (name "Net-(IC1-CT)") (class "Default")
      (node (ref "C_DELAY") (pin "1") (pinfunction "1_1") (pintype "passive"))
      (node (ref "IC1") (pin "5") (pinfunction "CT_5") (pintype "bidirectional"))
    )
    (net (code "32") (name "Net-(J2-PadA5)") (class "Default")
      (node (ref "J2") (pin "A5") (pinfunction "A5_A5") (pintype "bidirectional"))
      (node (ref "R2-USB1") (pin "2") (pinfunction "2_2") (pintype "passive"))
    )
    (net (code "33") (name "Net-(J2-PadB5)") (class "Default")
      (node (ref "J2") (pin "B5") (pinfunction "B5_B5") (pintype "bidirectional"))
      (node (ref "R2-USB") (pin "1") (pinfunction "1_1") (pintype "passive"))
    )
    (net (code "34") (name "Net-(MCP73831-PROG)") (class "Default")
      (node (ref "MCP73831") (pin "5") (pinfunction "PROG_5") (pintype "input"))
      (node (ref "R2_BAT") (pin "2") (pinfunction "2_2") (pintype "passive"))
    )
    (net (code "35") (name "Net-(MCP73831-STAT)") (class "Default")
      (node (ref "MCP73831") (pin "1") (pinfunction "STAT_1") (pintype "output"))
      (node (ref "R1_BAT") (pin "2") (pinfunction "2_2") (pintype "passive"))
    )
    (net (code "36") (name "PREVGH") (class "Default")
      (node (ref "D5") (pin "1") (pinfunction "K_1") (pintype "bidirectional"))
      (node (ref "EPD_C9") (pin "1") (pinfunction "1_1") (pintype "passive"))
      (node (ref "J1") (pin "21") (pinfunction "21_21") (pintype "bidirectional"))
    )
    (net (code "37") (name "PREVGL") (class "Default")
      (node (ref "D4") (pin "2") (pinfunction "A_2") (pintype "bidirectional"))
      (node (ref "EPD_C11") (pin "1") (pinfunction "1_1") (pintype "passive"))
      (node (ref "J1") (pin "23") (pinfunction "23_23") (pintype "bidirectional"))
    )
    (net (code "38") (name "RESE") (class "Default")
      (node (ref "J1") (pin "3") (pinfunction "3_3") (pintype "bidirectional"))
      (node (ref "Q3") (pin "2") (pinfunction "S_2") (pintype "bidirectional"))
      (node (ref "R3") (pin "2") (pinfunction "2_2") (pintype "passive"))
    )
    (net (code "39") (name "RESE'") (class "Default")
      (node (ref "R2") (pin "2") (pinfunction "2_2") (pintype "passive"))
      (node (ref "R3") (pin "1") (pinfunction "1_1") (pintype "passive"))
      (node (ref "SJ1") (pin "2") (pinfunction "2_2") (pintype "passive"))
    )
    (net (code "40") (name "RESET") (class "Default")
      (node (ref "C5") (pin "1") (pinfunction "1_1") (pintype "passive"))
      (node (ref "IC1") (pin "1") (pinfunction "VOUT_1") (pintype "bidirectional"))
      (node (ref "RESET_BUTTON") (pin "3") (pinfunction "3_3") (pintype "passive"))
      (node (ref "RESET_BUTTON") (pin "4") (pinfunction "4_4") (pintype "passive"))
      (node (ref "R_RESET") (pin "2") (pinfunction "2_2") (pintype "passive"))
      (node (ref "U2") (pin "3") (pinfunction "EN_3") (pintype "input"))
    )
    (net (code "41") (name "RTC_RST") (class "Default")
      (node (ref "U2") (pin "16") (pinfunction "IO18_16") (pintype "bidirectional"))
      (node (ref "U3") (pin "4") (pinfunction "~{RST}_4") (pintype "input"))
    )
    (net (code "42") (name "RX") (class "Default")
      (node (ref "TP2") (pin "TP") (pinfunction "TP_TP") (pintype "input"))
      (node (ref "U2") (pin "24") (pinfunction "RXD0/GPIO17_24") (pintype "bidirectional"))
    )
    (net (code "43") (name "SCK") (class "Default")
      (node (ref "D10") (pin "2") (pinfunction "2_2") (pintype "passive"))
      (node (ref "J1") (pin "13") (pinfunction "13_13") (pintype "bidirectional"))
      (node (ref "J4") (pin "P5") (pinfunction "CLK_P5") (pintype "bidirectional"))
      (node (ref "R6") (pin "1") (pinfunction "1_1") (pintype "passive"))
      (node (ref "TP8") (pin "TP") (pinfunction "TP_TP") (pintype "input"))
      (node (ref "U1") (pin "6") (pinfunction "CLK_6") (pintype "input"))
      (node (ref "U2") (pin "6") (pinfunction "IO6_6") (pintype "bidirectional"))
    )
    (net (code "44") (name "SCL") (class "Default")
      (node (ref "J3") (pin "4") (pinfunction "4_4") (pintype "passive"))
      (node (ref "R2-PINH") (pin "1") (pinfunction "1_1") (pintype "passive"))
      (node (ref "SENSOR2") (pin "4") (pinfunction "SCK_4") (pintype "input"))
      (node (ref "U2") (pin "20") (pinfunction "IO22_20") (pintype "bidirectional"))
      (node (ref "U3") (pin "16") (pinfunction "SCL_16") (pintype "input"))
      (node (ref "U4") (pin "7") (pinfunction "SCL_7") (pintype "input"))
    )
    (net (code "45") (name "SDA") (class "Default")
      (node (ref "J3") (pin "3") (pinfunction "3_3") (pintype "passive"))
      (node (ref "R1_PINH") (pin "1") (pinfunction "1_1") (pintype "passive"))
      (node (ref "SENSOR2") (pin "3") (pinfunction "SDI_3") (pintype "bidirectional"))
      (node (ref "U2") (pin "19") (pinfunction "IO21_19") (pintype "bidirectional"))
      (node (ref "U3") (pin "15") (pinfunction "SDA_15") (pintype "bidirectional"))
      (node (ref "U4") (pin "8") (pinfunction "SDA_8") (pintype "bidirectional"))
    )
    (net (code "46") (name "SRC") (class "Default")
      (node (ref "C4") (pin "2") (pinfunction "2_2") (pintype "passive"))
      (node (ref "D5") (pin "2") (pinfunction "A_2") (pintype "bidirectional"))
      (node (ref "L1") (pin "1") (pinfunction "1_1") (pintype "passive"))
      (node (ref "Q3") (pin "3") (pinfunction "D_3") (pintype "bidirectional"))
    )
    (net (code "47") (name "SS_SD") (class "Default")
      (node (ref "D8") (pin "2") (pinfunction "2_2") (pintype "passive"))
      (node (ref "J4") (pin "P2") (pinfunction "CD/DAT3_P2") (pintype "bidirectional"))
      (node (ref "R10") (pin "1") (pinfunction "1_1") (pintype "passive"))
      (node (ref "U2") (pin "4") (pinfunction "IO4_4") (pintype "bidirectional"))
    )
    (net (code "48") (name "TX") (class "Default")
      (node (ref "TP1") (pin "TP") (pinfunction "TP_TP") (pintype "input"))
      (node (ref "U2") (pin "25") (pinfunction "TXD0/GPIO16_25") (pintype "bidirectional"))
    )
    (net (code "49") (name "USB_D+") (class "Default")
      (node (ref "D1") (pin "4") (pinfunction "I/O2_2_4") (pintype "bidirectional"))
      (node (ref "U2") (pin "14") (pinfunction "IO13_14") (pintype "bidirectional"))
    )
    (net (code "50") (name "USB_D-") (class "Default")
      (node (ref "D1") (pin "6") (pinfunction "I/O1_2_6") (pintype "bidirectional"))
      (node (ref "U2") (pin "13") (pinfunction "IO12_13") (pintype "bidirectional"))
    )
    (net (code "51") (name "VBAT") (class "Default")
      (node (ref "C2_BAT") (pin "1") (pinfunction "1_1") (pintype "passive"))
      (node (ref "MCP73831") (pin "3") (pinfunction "VBAT_3") (pintype "power_in"))
      (node (ref "Q1") (pin "3") (pinfunction "D_3") (pintype "bidirectional"))
      (node (ref "TP3") (pin "TP") (pinfunction "TP_TP") (pintype "input"))
      (node (ref "U4") (pin "2") (pinfunction "CELL_2") (pintype "power_in"))
      (node (ref "U4") (pin "3") (pinfunction "VDD_3") (pintype "power_in"))
    )
    (net (code "52") (name "VBUS") (class "Default")
      (node (ref "C1_BAT") (pin "1") (pinfunction "1_1") (pintype "passive"))
      (node (ref "C4_USB") (pin "1") (pinfunction "1_1") (pintype "passive"))
      (node (ref "C5_USB") (pin "1") (pinfunction "1_1") (pintype "passive"))
      (node (ref "CHG_LED") (pin "A") (pinfunction "A_A") (pintype "passive"))
      (node (ref "D1") (pin "2") (pinfunction "GND_2") (pintype "bidirectional"))
      (node (ref "D2") (pin "2") (pinfunction "ANODE_2") (pintype "bidirectional"))
      (node (ref "MCP73831") (pin "4") (pinfunction "VIN_4") (pintype "power_in"))
      (node (ref "PFMF.050.1") (pin "2") (pinfunction "2_2") (pintype "passive"))
      (node (ref "Q1") (pin "1") (pinfunction "G_1") (pintype "bidirectional"))
      (node (ref "R1_PWRUSB") (pin "2") (pinfunction "2_2") (pintype "passive"))
      (node (ref "TP14") (pin "TP") (pinfunction "TP_TP") (pintype "input"))
    )
    (net (code "53") (name "VRTC") (class "Default")
      (node (ref "C10_SUPERCAP") (pin "2") (pinfunction "2_2") (pintype "passive"))
      (node (ref "C8") (pin "1") (pinfunction "1_1") (pintype "passive"))
      (node (ref "D7") (pin "1") (pinfunction "CATHODE_1") (pintype "bidirectional"))
      (node (ref "R_CAPACITOR") (pin "1") (pinfunction "1_1") (pintype "passive"))
      (node (ref "R_CAPACITOR") (pin "2") (pinfunction "2_2") (pintype "passive"))
      (node (ref "U3") (pin "14") (pinfunction "VBAT_14") (pintype "power_in"))
    )
    (net (code "54") (name "VUSB") (class "Default")
      (node (ref "J2") (pin "A4") (pinfunction "A4_A4") (pintype "bidirectional"))
      (node (ref "J2") (pin "A9") (pinfunction "A9_A9") (pintype "bidirectional"))
      (node (ref "J2") (pin "B4") (pinfunction "B4_B4") (pintype "bidirectional"))
      (node (ref "J2") (pin "B9") (pinfunction "B9_B9") (pintype "bidirectional"))
      (node (ref "PFMF.050.1") (pin "1") (pinfunction "1_1") (pintype "passive"))
    )
    (net (code "55") (name "unconnected-(IC1-NC-Pad4)") (class "Default")
      (node (ref "IC1") (pin "4") (pinfunction "NC_4") (pintype "no_connect"))
    )
    (net (code "56") (name "unconnected-(IC4-NC-Pad4)") (class "Default")
      (node (ref "IC4") (pin "4") (pinfunction "NC_4") (pintype "no_connect"))
    )
    (net (code "57") (name "unconnected-(J1-Pad1)") (class "Default")
      (node (ref "J1") (pin "1") (pinfunction "1_1") (pintype "bidirectional"))
    )
    (net (code "58") (name "unconnected-(J1-Pad6)") (class "Default")
      (node (ref "J1") (pin "6") (pinfunction "6_6") (pintype "bidirectional"))
    )
    (net (code "59") (name "unconnected-(J1-Pad7)") (class "Default")
      (node (ref "J1") (pin "7") (pinfunction "7_7") (pintype "bidirectional"))
    )
    (net (code "60") (name "unconnected-(J2-PadA8)") (class "Default")
      (node (ref "J2") (pin "A8") (pinfunction "A8_A8") (pintype "bidirectional"))
    )
    (net (code "61") (name "unconnected-(J2-PadB8)") (class "Default")
      (node (ref "J2") (pin "B8") (pinfunction "B8_B8") (pintype "bidirectional"))
    )
    (net (code "62") (name "unconnected-(J4-DAT1-PadP8)") (class "Default")
      (node (ref "J4") (pin "P8") (pinfunction "DAT1_P8") (pintype "bidirectional"))
    )
    (net (code "63") (name "unconnected-(J4-DAT2-PadP1)") (class "Default")
      (node (ref "J4") (pin "P1") (pinfunction "DAT2_P1") (pintype "bidirectional"))
    )
    (net (code "64") (name "unconnected-(J4-DETECTION_1-PadS1)") (class "Default")
      (node (ref "J4") (pin "S1") (pinfunction "DETECTION_1_S1") (pintype "bidirectional"))
    )
    (net (code "65") (name "unconnected-(J4-DETECTION_2-PadS2)") (class "Default")
      (node (ref "J4") (pin "S2") (pinfunction "DETECTION_2_S2") (pintype "bidirectional"))
    )
    (net (code "66") (name "unconnected-(U2-NC-Pad22)") (class "Default")
      (node (ref "U2") (pin "22") (pinfunction "NC_22") (pintype "no_connect"))
    )
    (net (code "67") (name "unconnected-(U4-~{ALERT}-Pad5)") (class "Default")
      (node (ref "U4") (pin "5") (pinfunction "~{ALERT}_5") (pintype "output"))
    )
  )
)
